# Audio.net
KiCad netlist of a schematic drawn in Altium Designer
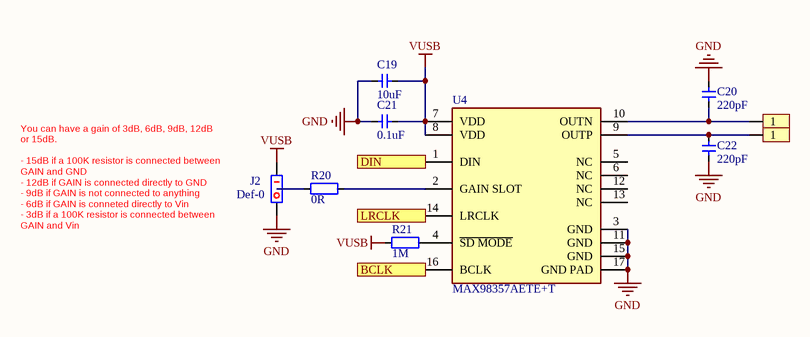
[diagram p0: Audio.SchDoc]

(export (version "E")
  (design (tool "Eeschema 10.0.6"))
  (components
    (comp (ref "*1") (value "SPEAKER") (footprint "SPEAKER") (libsource (lib "MyPcbLib") (part "SPEAKER")))
    (comp (ref "*2") (value "SPEAKER") (footprint "SPEAKER") (libsource (lib "MyPcbLib") (part "SPEAKER")))
    (comp (ref "C19")
      (value "10uF")
      (footprint "CAP_0402")
      (description "Capacitor")
      (libsource (lib "MyPcbLib") (part "电容-0402"))
    )
    (comp (ref "C20")
      (value "220pF")
      (footprint "CAP_0402")
      (description "Capacitor")
      (libsource (lib "MyPcbLib") (part "电容-0402"))
    )
    (comp (ref "C21")
      (value "0.1uF")
      (footprint "CAP_0402")
      (description "Capacitor")
      (libsource (lib "MyPcbLib") (part "电容-0402"))
    )
    (comp (ref "C22")
      (value "220pF")
      (footprint "CAP_0402")
      (description "Capacitor")
      (libsource (lib "MyPcbLib") (part "电容-0402"))
    )
    (comp (ref "J2")
      (value "Def-0")
      (footprint "jumper-3")
      (description "Resistor")
      (fields (field (name "PUBLISHER") "Altium Limited"))
      (libsource (lib "MyPcbLib") (part "选择跳线"))
    )
    (comp (ref "R20")
      (value "0R")
      (footprint "RES_0402")
      (description "Resistor")
      (libsource (lib "MyPcbLib") (part "电阻-0402"))
    )
    (comp (ref "R21")
      (value "1M")
      (footprint "RES_0402")
      (description "Resistor")
      (libsource (lib "MyPcbLib") (part "电阻-0402"))
    )
    (comp (ref "U4")
      (value "MAX98357AETE")
      (footprint "TQFN-16")
      (description "IC Amplifier IC 2-Channel (Stereo) Class D 16-TQFN (3x3)")
      (fields
        (field (name "MANUFACTURER") "Maxim Electronics")
        (field (name "MOUSER PART NUMBER") "700-MAX98357AETE+T")
        (field (name "PART NUMBER") "MAX98357AETE+T")
      )
      (libsource (lib "MyPcbLib") (part "MAX98357AETE"))
    )
  )
  (nets
    (net (code "1") (name "/BCLK") (class "Default")
      (node (ref "U4") (pin "16") (pinfunction "BCLK_16") (pintype "passive"))
    )
    (net (code "2") (name "/DIN") (class "Default")
      (node (ref "U4") (pin "1") (pinfunction "DIN_1") (pintype "passive"))
    )
    (net (code "3") (name "/LRCLK") (class "Default")
      (node (ref "U4") (pin "14") (pinfunction "LRCLK_14") (pintype "passive"))
    )
    (net (code "4") (name "GND") (class "Default")
      (node (ref "C19") (pin "1") (pinfunction "1_1") (pintype "passive"))
      (node (ref "C20") (pin "2") (pinfunction "2_2") (pintype "passive"))
      (node (ref "C21") (pin "1") (pinfunction "1_1") (pintype "passive"))
      (node (ref "C22") (pin "2") (pinfunction "2_2") (pintype "passive"))
      (node (ref "J2") (pin "1") (pinfunction "1_1") (pintype "passive"))
      (node (ref "U4") (pin "11") (pinfunction "GND_11") (pintype "passive"))
      (node (ref "U4") (pin "15") (pinfunction "GND_15") (pintype "passive"))
      (node (ref "U4") (pin "17") (pinfunction "GND_PAD_17") (pintype "passive"))
      (node (ref "U4") (pin "3") (pinfunction "GND_3") (pintype "passive"))
    )
    (net (code "5") (name "Net-(J2-Pad2)") (class "Default")
      (node (ref "J2") (pin "2") (pinfunction "2_2") (pintype "passive"))
      (node (ref "R20") (pin "1") (pinfunction "1_1") (pintype "passive"))
    )
    (net (code "6") (name "Net-(U4-GAIN_SLOT)") (class "Default")
      (node (ref "R20") (pin "2") (pinfunction "2_2") (pintype "passive"))
      (node (ref "U4") (pin "2") (pinfunction "GAIN_SLOT_2") (pintype "passive"))
    )
    (net (code "7") (name "Net-(U4-OUTN)") (class "Default")
      (node (ref "*1") (pin "1") (pinfunction "1_1") (pintype "passive"))
      (node (ref "C20") (pin "1") (pinfunction "1_1") (pintype "passive"))
      (node (ref "U4") (pin "10") (pinfunction "OUTN_10") (pintype "passive"))
    )
    (net (code "8") (name "Net-(U4-OUTP)") (class "Default")
      (node (ref "*2") (pin "1") (pinfunction "1_1") (pintype "passive"))
      (node (ref "C22") (pin "1") (pinfunction "1_1") (pintype "passive"))
      (node (ref "U4") (pin "9") (pinfunction "OUTP_9") (pintype "passive"))
    )
    (net (code "9") (name "Net-(U4-~{SD_MODE})") (class "Default")
      (node (ref "R21") (pin "2") (pinfunction "2_2") (pintype "passive"))
      (node (ref "U4") (pin "4") (pinfunction "~{SD_MODE}_4") (pintype "passive"))
    )
    (net (code "10") (name "VUSB") (class "Default")
      (node (ref "C19") (pin "2") (pinfunction "2_2") (pintype "passive"))
      (node (ref "C21") (pin "2") (pinfunction "2_2") (pintype "passive"))
      (node (ref "J2") (pin "3") (pinfunction "3_3") (pintype "passive"))
      (node (ref "R21") (pin "1") (pinfunction "1_1") (pintype "passive"))
      (node (ref "U4") (pin "7") (pinfunction "VDD_7") (pintype "passive"))
      (node (ref "U4") (pin "8") (pinfunction "VDD_8") (pintype "passive"))
    )
    (net (code "11") (name "unconnected-(U4-NC-Pad5)") (class "Default")
      (node (ref "U4") (pin "5") (pinfunction "NC_5") (pintype "passive"))
    )
    (net (code "12") (name "unconnected-(U4-NC-Pad6)") (class "Default")
      (node (ref "U4") (pin "6") (pinfunction "NC_6") (pintype "passive"))
    )
    (net (code "13") (name "unconnected-(U4-NC-Pad12)") (class "Default")
      (node (ref "U4") (pin "12") (pinfunction "NC_12") (pintype "passive"))
    )
    (net (code "14") (name "unconnected-(U4-NC-Pad13)") (class "Default")
      (node (ref "U4") (pin "13") (pinfunction "NC_13") (pintype "passive"))
    )
  )
)
